# Main.net
KiCad netlist of a schematic drawn in Altium Designer
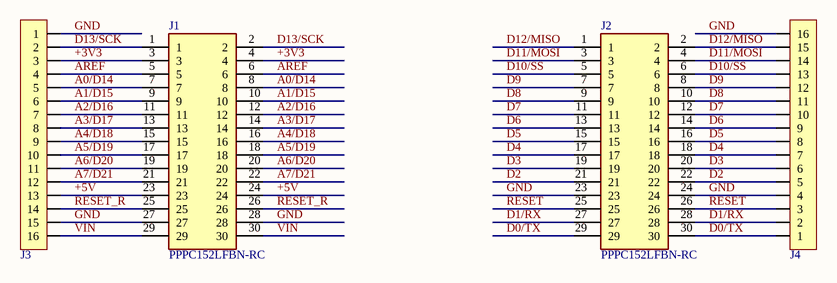
[diagram p0: Main.SchDoc]

(export (version "E")
  (design (tool "Eeschema 10.0.6"))
  (components
    (comp (ref "J1")
      (value "PPPC152LFBN-RC")
      (footprint "RHDR30W80P254_2X15_3860X508X880P")
      (description "CONN HDR 30POS 0.1 GOLD PCB")
      (fields (field (name "MF") "Sullins"))
      (libsource (lib "OF_Connectors") (part "PPPC152LFBN-RC"))
    )
    (comp (ref "J2")
      (value "PPPC152LFBN-RC")
      (footprint "RHDR30W80P254_2X15_3860X508X880P")
      (description "CONN HDR 30POS 0.1 GOLD PCB")
      (fields (field (name "MF") "Sullins"))
      (libsource (lib "OF_Connectors") (part "PPPC152LFBN-RC"))
    )
    (comp (ref "J3")
      (value "22TW-277")
      (footprint "MK125002GO")
      (description "CONN MORS.CS 16v p3,5 10A aLING.VER BLACK")
      (fields (field (name "MANUFACTURER") "4U CON"))
      (libsource (lib "OF_Connectors") (part "J0275-A.6"))
    )
    (comp (ref "J4")
      (value "22TW-277")
      (footprint "MK125002GO")
      (description "CONN MORS.CS 16v p3,5 10A aLING.VER BLACK")
      (fields (field (name "MANUFACTURER") "4U CON"))
      (libsource (lib "") (part "J0275-A.6_1"))
    )
  )
  (nets
    (net (code "1") (name "/+3V3") (class "Default")
      (node (ref "J1") (pin "3") (pinfunction "3_3") (pintype "passive"))
      (node (ref "J1") (pin "4") (pinfunction "4_4") (pintype "passive"))
      (node (ref "J3") (pin "3") (pinfunction "3_3") (pintype "passive"))
    )
    (net (code "2") (name "/+5V") (class "Default")
      (node (ref "J1") (pin "23") (pinfunction "23_23") (pintype "passive"))
      (node (ref "J1") (pin "24") (pinfunction "24_24") (pintype "passive"))
      (node (ref "J3") (pin "13") (pinfunction "13_13") (pintype "passive"))
    )
    (net (code "3") (name "/A0{slash}D14") (class "Default")
      (node (ref "J1") (pin "7") (pinfunction "7_7") (pintype "passive"))
      (node (ref "J1") (pin "8") (pinfunction "8_8") (pintype "passive"))
      (node (ref "J3") (pin "5") (pinfunction "5_5") (pintype "passive"))
    )
    (net (code "4") (name "/A1{slash}D15") (class "Default")
      (node (ref "J1") (pin "10") (pinfunction "10_10") (pintype "passive"))
      (node (ref "J1") (pin "9") (pinfunction "9_9") (pintype "passive"))
      (node (ref "J3") (pin "6") (pinfunction "6_6") (pintype "passive"))
    )
    (net (code "5") (name "/A2{slash}D16") (class "Default")
      (node (ref "J1") (pin "11") (pinfunction "11_11") (pintype "passive"))
      (node (ref "J1") (pin "12") (pinfunction "12_12") (pintype "passive"))
      (node (ref "J3") (pin "7") (pinfunction "7_7") (pintype "passive"))
    )
    (net (code "6") (name "/A3{slash}D17") (class "Default")
      (node (ref "J1") (pin "13") (pinfunction "13_13") (pintype "passive"))
      (node (ref "J1") (pin "14") (pinfunction "14_14") (pintype "passive"))
      (node (ref "J3") (pin "8") (pinfunction "8_8") (pintype "passive"))
    )
    (net (code "7") (name "/A4{slash}D18") (class "Default")
      (node (ref "J1") (pin "15") (pinfunction "15_15") (pintype "passive"))
      (node (ref "J1") (pin "16") (pinfunction "16_16") (pintype "passive"))
      (node (ref "J3") (pin "9") (pinfunction "9_9") (pintype "passive"))
    )
    (net (code "8") (name "/A5{slash}D19") (class "Default")
      (node (ref "J1") (pin "17") (pinfunction "17_17") (pintype "passive"))
      (node (ref "J1") (pin "18") (pinfunction "18_18") (pintype "passive"))
      (node (ref "J3") (pin "10") (pinfunction "10_10") (pintype "passive"))
    )
    (net (code "9") (name "/A6{slash}D20") (class "Default")
      (node (ref "J1") (pin "19") (pinfunction "19_19") (pintype "passive"))
      (node (ref "J1") (pin "20") (pinfunction "20_20") (pintype "passive"))
      (node (ref "J3") (pin "11") (pinfunction "11_11") (pintype "passive"))
    )
    (net (code "10") (name "/A7{slash}D21") (class "Default")
      (node (ref "J1") (pin "21") (pinfunction "21_21") (pintype "passive"))
      (node (ref "J1") (pin "22") (pinfunction "22_22") (pintype "passive"))
      (node (ref "J3") (pin "12") (pinfunction "12_12") (pintype "passive"))
    )
    (net (code "11") (name "/AREF") (class "Default")
      (node (ref "J1") (pin "5") (pinfunction "5_5") (pintype "passive"))
      (node (ref "J1") (pin "6") (pinfunction "6_6") (pintype "passive"))
      (node (ref "J3") (pin "4") (pinfunction "4_4") (pintype "passive"))
    )
    (net (code "12") (name "/D0{slash}TX") (class "Default")
      (node (ref "J2") (pin "29") (pinfunction "29_29") (pintype "passive"))
      (node (ref "J2") (pin "30") (pinfunction "30_30") (pintype "passive"))
      (node (ref "J4") (pin "1") (pinfunction "1_1") (pintype "passive"))
    )
    (net (code "13") (name "/D1{slash}RX") (class "Default")
      (node (ref "J2") (pin "27") (pinfunction "27_27") (pintype "passive"))
      (node (ref "J2") (pin "28") (pinfunction "28_28") (pintype "passive"))
      (node (ref "J4") (pin "2") (pinfunction "2_2") (pintype "passive"))
    )
    (net (code "14") (name "/D2") (class "Default")
      (node (ref "J2") (pin "21") (pinfunction "21_21") (pintype "passive"))
      (node (ref "J2") (pin "22") (pinfunction "22_22") (pintype "passive"))
      (node (ref "J4") (pin "5") (pinfunction "5_5") (pintype "passive"))
    )
    (net (code "15") (name "/D3") (class "Default")
      (node (ref "J2") (pin "19") (pinfunction "19_19") (pintype "passive"))
      (node (ref "J2") (pin "20") (pinfunction "20_20") (pintype "passive"))
      (node (ref "J4") (pin "6") (pinfunction "6_6") (pintype "passive"))
    )
    (net (code "16") (name "/D4") (class "Default")
      (node (ref "J2") (pin "17") (pinfunction "17_17") (pintype "passive"))
      (node (ref "J2") (pin "18") (pinfunction "18_18") (pintype "passive"))
      (node (ref "J4") (pin "7") (pinfunction "7_7") (pintype "passive"))
    )
    (net (code "17") (name "/D5") (class "Default")
      (node (ref "J2") (pin "15") (pinfunction "15_15") (pintype "passive"))
      (node (ref "J2") (pin "16") (pinfunction "16_16") (pintype "passive"))
      (node (ref "J4") (pin "8") (pinfunction "8_8") (pintype "passive"))
    )
    (net (code "18") (name "/D6") (class "Default")
      (node (ref "J2") (pin "13") (pinfunction "13_13") (pintype "passive"))
      (node (ref "J2") (pin "14") (pinfunction "14_14") (pintype "passive"))
      (node (ref "J4") (pin "9") (pinfunction "9_9") (pintype "passive"))
    )
    (net (code "19") (name "/D7") (class "Default")
      (node (ref "J2") (pin "11") (pinfunction "11_11") (pintype "passive"))
      (node (ref "J2") (pin "12") (pinfunction "12_12") (pintype "passive"))
      (node (ref "J4") (pin "10") (pinfunction "10_10") (pintype "passive"))
    )
    (net (code "20") (name "/D8") (class "Default")
      (node (ref "J2") (pin "10") (pinfunction "10_10") (pintype "passive"))
      (node (ref "J2") (pin "9") (pinfunction "9_9") (pintype "passive"))
      (node (ref "J4") (pin "11") (pinfunction "11_11") (pintype "passive"))
    )
    (net (code "21") (name "/D9") (class "Default")
      (node (ref "J2") (pin "7") (pinfunction "7_7") (pintype "passive"))
      (node (ref "J2") (pin "8") (pinfunction "8_8") (pintype "passive"))
      (node (ref "J4") (pin "12") (pinfunction "12_12") (pintype "passive"))
    )
    (net (code "22") (name "/D10{slash}SS") (class "Default")
      (node (ref "J2") (pin "5") (pinfunction "5_5") (pintype "passive"))
      (node (ref "J2") (pin "6") (pinfunction "6_6") (pintype "passive"))
      (node (ref "J4") (pin "13") (pinfunction "13_13") (pintype "passive"))
    )
    (net (code "23") (name "/D11{slash}MOSI") (class "Default")
      (node (ref "J2") (pin "3") (pinfunction "3_3") (pintype "passive"))
      (node (ref "J2") (pin "4") (pinfunction "4_4") (pintype "passive"))
      (node (ref "J4") (pin "14") (pinfunction "14_14") (pintype "passive"))
    )
    (net (code "24") (name "/D12{slash}MISO") (class "Default")
      (node (ref "J2") (pin "1") (pinfunction "1_1") (pintype "passive"))
      (node (ref "J2") (pin "2") (pinfunction "2_2") (pintype "passive"))
      (node (ref "J4") (pin "15") (pinfunction "15_15") (pintype "passive"))
    )
    (net (code "25") (name "/D13{slash}SCK") (class "Default")
      (node (ref "J1") (pin "1") (pinfunction "1_1") (pintype "passive"))
      (node (ref "J1") (pin "2") (pinfunction "2_2") (pintype "passive"))
      (node (ref "J3") (pin "2") (pinfunction "2_2") (pintype "passive"))
    )
    (net (code "26") (name "/GND") (class "Default")
      (node (ref "J1") (pin "27") (pinfunction "27_27") (pintype "passive"))
      (node (ref "J1") (pin "28") (pinfunction "28_28") (pintype "passive"))
      (node (ref "J2") (pin "23") (pinfunction "23_23") (pintype "passive"))
      (node (ref "J2") (pin "24") (pinfunction "24_24") (pintype "passive"))
      (node (ref "J3") (pin "1") (pinfunction "1_1") (pintype "passive"))
      (node (ref "J3") (pin "15") (pinfunction "15_15") (pintype "passive"))
      (node (ref "J4") (pin "16") (pinfunction "16_16") (pintype "passive"))
      (node (ref "J4") (pin "4") (pinfunction "4_4") (pintype "passive"))
    )
    (net (code "27") (name "/RESET") (class "Default")
      (node (ref "J2") (pin "25") (pinfunction "25_25") (pintype "passive"))
      (node (ref "J2") (pin "26") (pinfunction "26_26") (pintype "passive"))
      (node (ref "J4") (pin "3") (pinfunction "3_3") (pintype "passive"))
    )
    (net (code "28") (name "/RESET_R") (class "Default")
      (node (ref "J1") (pin "25") (pinfunction "25_25") (pintype "passive"))
      (node (ref "J1") (pin "26") (pinfunction "26_26") (pintype "passive"))
      (node (ref "J3") (pin "14") (pinfunction "14_14") (pintype "passive"))
    )
    (net (code "29") (name "/VIN") (class "Default")
      (node (ref "J1") (pin "29") (pinfunction "29_29") (pintype "passive"))
      (node (ref "J1") (pin "30") (pinfunction "30_30") (pintype "passive"))
      (node (ref "J3") (pin "16") (pinfunction "16_16") (pintype "passive"))
    )
  )
)
